# 8button-8eopixel.net
KiCad netlist of a schematic drawn in Altium Designer
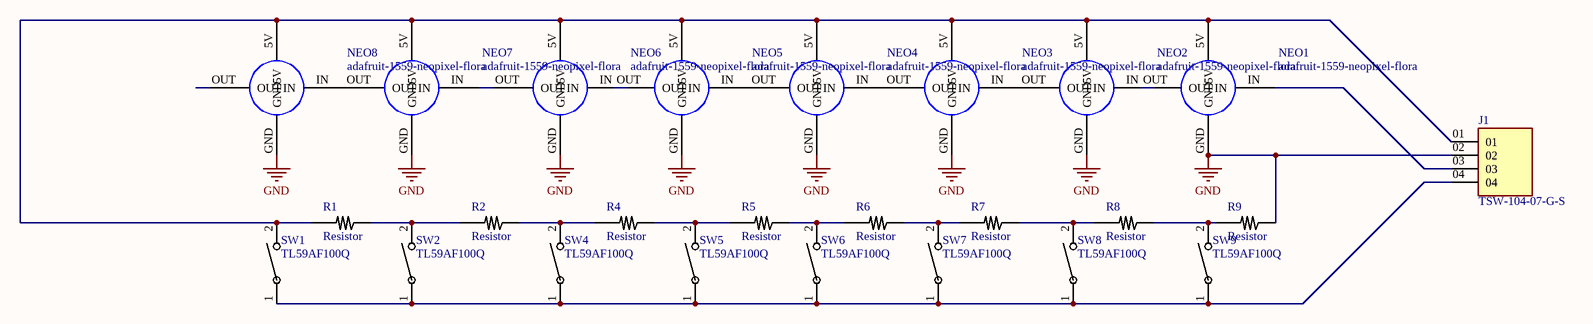
[diagram p0: 8button-8eopixel.SchDoc]

(export (version "E")
  (design (tool "Eeschema 10.0.6"))
  (components
    (comp (ref "J1")
      (value "TSW-104-07-G-S")
      (footprint "SAMTEC_TSW-104-07-G-S")
      (fields (field (name "MP") "altium_native_batch"))
      (libsource (lib "SchlibLafe") (part "TSW-104-07-G-S"))
    )
    (comp (ref "NEO1")
      (value "adafruit-1559-neopixel-flora")
      (footprint "adafruit-1559-neopixel-flora")
      (libsource (lib "SchlibLafe") (part "adafruit-1559-neopixel-flora"))
    )
    (comp (ref "NEO2")
      (value "adafruit-1559-neopixel-flora")
      (footprint "adafruit-1559-neopixel-flora")
      (libsource (lib "SchlibLafe") (part "adafruit-1559-neopixel-flora"))
    )
    (comp (ref "NEO3")
      (value "adafruit-1559-neopixel-flora")
      (footprint "adafruit-1559-neopixel-flora")
      (libsource (lib "SchlibLafe") (part "adafruit-1559-neopixel-flora"))
    )
    (comp (ref "NEO4")
      (value "adafruit-1559-neopixel-flora")
      (footprint "adafruit-1559-neopixel-flora")
      (libsource (lib "SchlibLafe") (part "adafruit-1559-neopixel-flora"))
    )
    (comp (ref "NEO5")
      (value "adafruit-1559-neopixel-flora")
      (footprint "adafruit-1559-neopixel-flora")
      (libsource (lib "SchlibLafe") (part "adafruit-1559-neopixel-flora"))
    )
    (comp (ref "NEO6")
      (value "adafruit-1559-neopixel-flora")
      (footprint "adafruit-1559-neopixel-flora")
      (libsource (lib "SchlibLafe") (part "adafruit-1559-neopixel-flora"))
    )
    (comp (ref "NEO7")
      (value "adafruit-1559-neopixel-flora")
      (footprint "adafruit-1559-neopixel-flora")
      (libsource (lib "SchlibLafe") (part "adafruit-1559-neopixel-flora"))
    )
    (comp (ref "NEO8")
      (value "adafruit-1559-neopixel-flora")
      (footprint "adafruit-1559-neopixel-flora")
      (libsource (lib "SchlibLafe") (part "adafruit-1559-neopixel-flora"))
    )
    (comp (ref "R1")
      (value "Resistor")
      (footprint "thruhole resistor")
      (libsource (lib "SchlibLafe") (part "Resistor"))
    )
    (comp (ref "R2")
      (value "Resistor")
      (footprint "thruhole resistor")
      (libsource (lib "SchlibLafe") (part "Resistor"))
    )
    (comp (ref "R4")
      (value "Resistor")
      (footprint "thruhole resistor")
      (libsource (lib "SchlibLafe") (part "Resistor"))
    )
    (comp (ref "R5")
      (value "Resistor")
      (footprint "thruhole resistor")
      (libsource (lib "SchlibLafe") (part "Resistor"))
    )
    (comp (ref "R6")
      (value "Resistor")
      (footprint "thruhole resistor")
      (libsource (lib "SchlibLafe") (part "Resistor"))
    )
    (comp (ref "R7")
      (value "Resistor")
      (footprint "thruhole resistor")
      (libsource (lib "SchlibLafe") (part "Resistor"))
    )
    (comp (ref "R8")
      (value "Resistor")
      (footprint "thruhole resistor")
      (libsource (lib "SchlibLafe") (part "Resistor"))
    )
    (comp (ref "R9")
      (value "Resistor")
      (footprint "thruhole resistor")
      (libsource (lib "SchlibLafe") (part "Resistor"))
    )
    (comp (ref "SW1")
      (value "TL59AF100Q")
      (footprint "SW_TL59AF100Q_EWI")
      (description "No Description Available")
      (fields (field (name "COPYRIGHT") "Copyright (C) 2024 Ultra Librarian. All rights reserved."))
      (libsource (lib "SchlibLafe") (part "TL59AF100Q"))
    )
    (comp (ref "SW2")
      (value "TL59AF100Q")
      (footprint "SW_TL59AF100Q_EWI")
      (description "No Description Available")
      (fields (field (name "COPYRIGHT") "Copyright (C) 2024 Ultra Librarian. All rights reserved."))
      (libsource (lib "SchlibLafe") (part "TL59AF100Q"))
    )
    (comp (ref "SW4")
      (value "TL59AF100Q")
      (footprint "SW_TL59AF100Q_EWI")
      (description "No Description Available")
      (fields (field (name "COPYRIGHT") "Copyright (C) 2024 Ultra Librarian. All rights reserved."))
      (libsource (lib "SchlibLafe") (part "TL59AF100Q"))
    )
    (comp (ref "SW5")
      (value "TL59AF100Q")
      (footprint "SW_TL59AF100Q_EWI")
      (description "No Description Available")
      (fields (field (name "COPYRIGHT") "Copyright (C) 2024 Ultra Librarian. All rights reserved."))
      (libsource (lib "SchlibLafe") (part "TL59AF100Q"))
    )
    (comp (ref "SW6")
      (value "TL59AF100Q")
      (footprint "SW_TL59AF100Q_EWI")
      (description "No Description Available")
      (fields (field (name "COPYRIGHT") "Copyright (C) 2024 Ultra Librarian. All rights reserved."))
      (libsource (lib "SchlibLafe") (part "TL59AF100Q"))
    )
    (comp (ref "SW7")
      (value "TL59AF100Q")
      (footprint "SW_TL59AF100Q_EWI")
      (description "No Description Available")
      (fields (field (name "COPYRIGHT") "Copyright (C) 2024 Ultra Librarian. All rights reserved."))
      (libsource (lib "SchlibLafe") (part "TL59AF100Q"))
    )
    (comp (ref "SW8")
      (value "TL59AF100Q")
      (footprint "SW_TL59AF100Q_EWI")
      (description "No Description Available")
      (fields (field (name "COPYRIGHT") "Copyright (C) 2024 Ultra Librarian. All rights reserved."))
      (libsource (lib "SchlibLafe") (part "TL59AF100Q"))
    )
    (comp (ref "SW9")
      (value "TL59AF100Q")
      (footprint "SW_TL59AF100Q_EWI")
      (description "No Description Available")
      (fields (field (name "COPYRIGHT") "Copyright (C) 2024 Ultra Librarian. All rights reserved."))
      (libsource (lib "SchlibLafe") (part "TL59AF100Q"))
    )
  )
  (nets
    (net (code "1") (name "GND") (class "Default")
      (node (ref "J1") (pin "02") (pinfunction "02_02") (pintype "passive"))
      (node (ref "NEO1") (pin "GND") (pinfunction "GND_GND") (pintype "passive"))
      (node (ref "NEO2") (pin "GND") (pinfunction "GND_GND") (pintype "passive"))
      (node (ref "NEO3") (pin "GND") (pinfunction "GND_GND") (pintype "passive"))
      (node (ref "NEO4") (pin "GND") (pinfunction "GND_GND") (pintype "passive"))
      (node (ref "NEO5") (pin "GND") (pinfunction "GND_GND") (pintype "passive"))
      (node (ref "NEO6") (pin "GND") (pinfunction "GND_GND") (pintype "passive"))
      (node (ref "NEO7") (pin "GND") (pinfunction "GND_GND") (pintype "passive"))
      (node (ref "NEO8") (pin "GND") (pinfunction "GND_GND") (pintype "passive"))
      (node (ref "R9") (pin "1") (pinfunction "1_1") (pintype "passive"))
    )
    (net (code "2") (name "Net-(J1-Pad01)") (class "Default")
      (node (ref "J1") (pin "01") (pinfunction "01_01") (pintype "passive"))
      (node (ref "NEO1") (pin "5V") (pinfunction "5V_5V") (pintype "passive"))
      (node (ref "NEO2") (pin "5V") (pinfunction "5V_5V") (pintype "passive"))
      (node (ref "NEO3") (pin "5V") (pinfunction "5V_5V") (pintype "passive"))
      (node (ref "NEO4") (pin "5V") (pinfunction "5V_5V") (pintype "passive"))
      (node (ref "NEO5") (pin "5V") (pinfunction "5V_5V") (pintype "passive"))
      (node (ref "NEO6") (pin "5V") (pinfunction "5V_5V") (pintype "passive"))
      (node (ref "NEO7") (pin "5V") (pinfunction "5V_5V") (pintype "passive"))
      (node (ref "NEO8") (pin "5V") (pinfunction "5V_5V") (pintype "passive"))
      (node (ref "R1") (pin "2") (pinfunction "2_2") (pintype "passive"))
      (node (ref "SW1") (pin "2") (pinfunction "2_2") (pintype "passive"))
    )
    (net (code "3") (name "Net-(J1-Pad03)") (class "Default")
      (node (ref "J1") (pin "03") (pinfunction "03_03") (pintype "passive"))
      (node (ref "NEO1") (pin "IN") (pinfunction "IN_IN") (pintype "passive"))
    )
    (net (code "4") (name "Net-(J1-Pad04)") (class "Default")
      (node (ref "J1") (pin "04") (pinfunction "04_04") (pintype "passive"))
      (node (ref "SW1") (pin "1") (pinfunction "1_1") (pintype "passive"))
      (node (ref "SW2") (pin "1") (pinfunction "1_1") (pintype "passive"))
      (node (ref "SW4") (pin "1") (pinfunction "1_1") (pintype "passive"))
      (node (ref "SW5") (pin "1") (pinfunction "1_1") (pintype "passive"))
      (node (ref "SW6") (pin "1") (pinfunction "1_1") (pintype "passive"))
      (node (ref "SW7") (pin "1") (pinfunction "1_1") (pintype "passive"))
      (node (ref "SW8") (pin "1") (pinfunction "1_1") (pintype "passive"))
      (node (ref "SW9") (pin "1") (pinfunction "1_1") (pintype "passive"))
    )
    (net (code "5") (name "Net-(NEO1-PadOUT)") (class "Default")
      (node (ref "NEO1") (pin "OUT") (pinfunction "OUT_OUT") (pintype "passive"))
      (node (ref "NEO2") (pin "IN") (pinfunction "IN_IN") (pintype "passive"))
    )
    (net (code "6") (name "Net-(NEO2-PadOUT)") (class "Default")
      (node (ref "NEO2") (pin "OUT") (pinfunction "OUT_OUT") (pintype "passive"))
      (node (ref "NEO3") (pin "IN") (pinfunction "IN_IN") (pintype "passive"))
    )
    (net (code "7") (name "Net-(NEO3-PadOUT)") (class "Default")
      (node (ref "NEO3") (pin "OUT") (pinfunction "OUT_OUT") (pintype "passive"))
      (node (ref "NEO4") (pin "IN") (pinfunction "IN_IN") (pintype "passive"))
    )
    (net (code "8") (name "Net-(NEO4-PadOUT)") (class "Default")
      (node (ref "NEO4") (pin "OUT") (pinfunction "OUT_OUT") (pintype "passive"))
      (node (ref "NEO5") (pin "IN") (pinfunction "IN_IN") (pintype "passive"))
    )
    (net (code "9") (name "Net-(NEO5-PadOUT)") (class "Default")
      (node (ref "NEO5") (pin "OUT") (pinfunction "OUT_OUT") (pintype "passive"))
      (node (ref "NEO6") (pin "IN") (pinfunction "IN_IN") (pintype "passive"))
    )
    (net (code "10") (name "Net-(NEO6-PadOUT)") (class "Default")
      (node (ref "NEO6") (pin "OUT") (pinfunction "OUT_OUT") (pintype "passive"))
      (node (ref "NEO7") (pin "IN") (pinfunction "IN_IN") (pintype "passive"))
    )
    (net (code "11") (name "Net-(NEO7-PadOUT)") (class "Default")
      (node (ref "NEO7") (pin "OUT") (pinfunction "OUT_OUT") (pintype "passive"))
      (node (ref "NEO8") (pin "IN") (pinfunction "IN_IN") (pintype "passive"))
    )
    (net (code "12") (name "Net-(R1-Pad1)") (class "Default")
      (node (ref "R1") (pin "1") (pinfunction "1_1") (pintype "passive"))
      (node (ref "R2") (pin "2") (pinfunction "2_2") (pintype "passive"))
      (node (ref "SW2") (pin "2") (pinfunction "2_2") (pintype "passive"))
    )
    (net (code "13") (name "Net-(R2-Pad1)") (class "Default")
      (node (ref "R2") (pin "1") (pinfunction "1_1") (pintype "passive"))
      (node (ref "R4") (pin "2") (pinfunction "2_2") (pintype "passive"))
      (node (ref "SW4") (pin "2") (pinfunction "2_2") (pintype "passive"))
    )
    (net (code "14") (name "Net-(R4-Pad1)") (class "Default")
      (node (ref "R4") (pin "1") (pinfunction "1_1") (pintype "passive"))
      (node (ref "R5") (pin "2") (pinfunction "2_2") (pintype "passive"))
      (node (ref "SW5") (pin "2") (pinfunction "2_2") (pintype "passive"))
    )
    (net (code "15") (name "Net-(R5-Pad1)") (class "Default")
      (node (ref "R5") (pin "1") (pinfunction "1_1") (pintype "passive"))
      (node (ref "R6") (pin "2") (pinfunction "2_2") (pintype "passive"))
      (node (ref "SW6") (pin "2") (pinfunction "2_2") (pintype "passive"))
    )
    (net (code "16") (name "Net-(R6-Pad1)") (class "Default")
      (node (ref "R6") (pin "1") (pinfunction "1_1") (pintype "passive"))
      (node (ref "R7") (pin "2") (pinfunction "2_2") (pintype "passive"))
      (node (ref "SW7") (pin "2") (pinfunction "2_2") (pintype "passive"))
    )
    (net (code "17") (name "Net-(R7-Pad1)") (class "Default")
      (node (ref "R7") (pin "1") (pinfunction "1_1") (pintype "passive"))
      (node (ref "R8") (pin "2") (pinfunction "2_2") (pintype "passive"))
      (node (ref "SW8") (pin "2") (pinfunction "2_2") (pintype "passive"))
    )
    (net (code "18") (name "Net-(R8-Pad1)") (class "Default")
      (node (ref "R8") (pin "1") (pinfunction "1_1") (pintype "passive"))
      (node (ref "R9") (pin "2") (pinfunction "2_2") (pintype "passive"))
      (node (ref "SW9") (pin "2") (pinfunction "2_2") (pintype "passive"))
    )
    (net (code "19") (name "unconnected-(NEO8-PadOUT)") (class "Default")
      (node (ref "NEO8") (pin "OUT") (pinfunction "OUT_OUT") (pintype "passive"))
    )
  )
)
